# PiModulos_V2_-_Mayonaise.net
KiCad netlist of a schematic drawn in Altium Designer
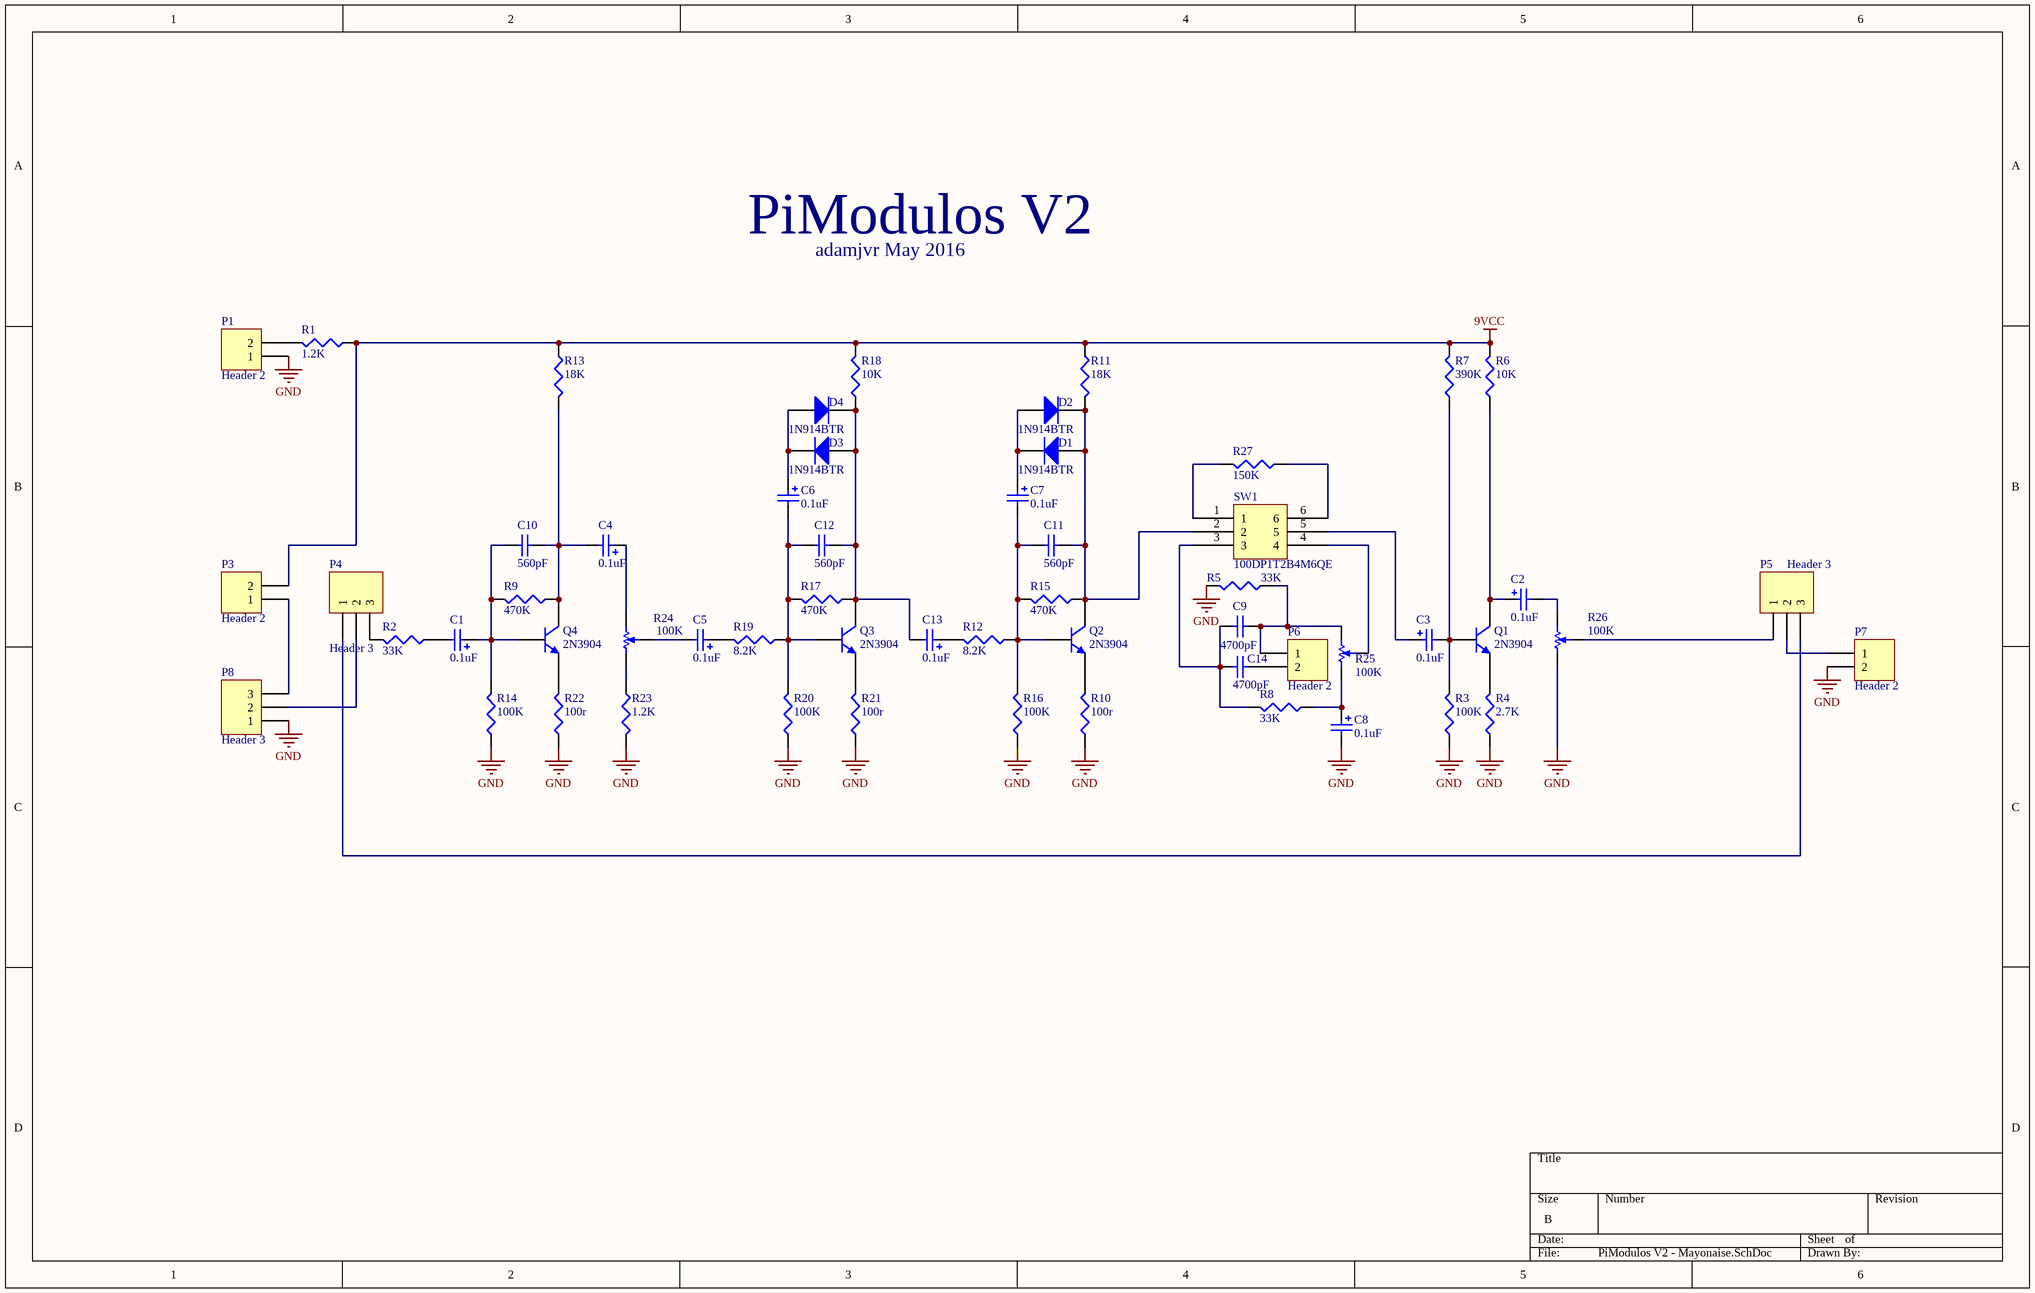
[diagram p0: PiModulos V2 - Mayonaise.SchDoc]

(export (version "E")
  (design (tool "Eeschema 10.0.6"))
  (components
    (comp (ref "C1")
      (value "0.1uF")
      (footprint "5X12.5mmCAP")
      (description "CAP ALUM 0.1UF 20% 100V RADIAL")
      (fields
        (field (name "MFR") "Nichicon")
        (field (name "TOLERANCE") "20%")
        (field (name "DESIGNER") "Adam Vadala-Roth")
      )
      (libsource (lib "AudioPartLib") (part "UFG2A0R1MDM1TD"))
    )
    (comp (ref "C2")
      (value "0.1uF")
      (footprint "5X12.5mmCAP")
      (description "CAP ALUM 0.1UF 20% 100V RADIAL")
      (fields
        (field (name "MFR") "Nichicon")
        (field (name "TOLERANCE") "20%")
        (field (name "DESIGNER") "Adam Vadala-Roth")
      )
      (libsource (lib "AudioPartLib") (part "UFG2A0R1MDM1TD"))
    )
    (comp (ref "C3")
      (value "0.1uF")
      (footprint "5X12.5mmCAP")
      (description "CAP ALUM 0.1UF 20% 100V RADIAL")
      (fields
        (field (name "MFR") "Nichicon")
        (field (name "TOLERANCE") "20%")
        (field (name "DESIGNER") "Adam Vadala-Roth")
      )
      (libsource (lib "AudioPartLib") (part "UFG2A0R1MDM1TD"))
    )
    (comp (ref "C4")
      (value "0.1uF")
      (footprint "5X12.5mmCAP")
      (description "CAP ALUM 0.1UF 20% 100V RADIAL")
      (fields
        (field (name "MFR") "Nichicon")
        (field (name "TOLERANCE") "20%")
        (field (name "DESIGNER") "Adam Vadala-Roth")
      )
      (libsource (lib "AudioPartLib") (part "UFG2A0R1MDM1TD"))
    )
    (comp (ref "C5")
      (value "0.1uF")
      (footprint "5X12.5mmCAP")
      (description "CAP ALUM 0.1UF 20% 100V RADIAL")
      (fields
        (field (name "MFR") "Nichicon")
        (field (name "TOLERANCE") "20%")
        (field (name "DESIGNER") "Adam Vadala-Roth")
      )
      (libsource (lib "AudioPartLib") (part "UFG2A0R1MDM1TD"))
    )
    (comp (ref "C6")
      (value "0.1uF")
      (footprint "5X12.5mmCAP")
      (description "CAP ALUM 0.1UF 20% 100V RADIAL")
      (fields
        (field (name "MFR") "Nichicon")
        (field (name "TOLERANCE") "20%")
        (field (name "DESIGNER") "Adam Vadala-Roth")
      )
      (libsource (lib "AudioPartLib") (part "UFG2A0R1MDM1TD"))
    )
    (comp (ref "C7")
      (value "0.1uF")
      (footprint "5X12.5mmCAP")
      (description "CAP ALUM 0.1UF 20% 100V RADIAL")
      (fields
        (field (name "MFR") "Nichicon")
        (field (name "TOLERANCE") "20%")
        (field (name "DESIGNER") "Adam Vadala-Roth")
      )
      (libsource (lib "AudioPartLib") (part "UFG2A0R1MDM1TD"))
    )
    (comp (ref "C8")
      (value "0.1uF")
      (footprint "5X12.5mmCAP")
      (description "CAP ALUM 0.1UF 20% 100V RADIAL")
      (fields
        (field (name "MFR") "Nichicon")
        (field (name "TOLERANCE") "20%")
        (field (name "DESIGNER") "Adam Vadala-Roth")
      )
      (libsource (lib "AudioPartLib") (part "UFG2A0R1MDM1TD"))
    )
    (comp (ref "C9")
      (value "4700pF")
      (footprint "VY2472M49Y5US63V7")
      (fields
        (field (name "MFR") "Vishay-BC-Components")
        (field (name "TOLERANCE") "20%")
        (field (name "VOLTAGE") "440VAC")
        (field (name "DESIGNER") "Adam Vadala-Roth")
      )
      (libsource (lib "AudioPartLib") (part "VY2472M49Y5US63V7"))
    )
    (comp (ref "C10")
      (value "560pF")
      (footprint "C0805")
      (fields
        (field (name "MFR") "Samsung-Electro-Mechanics-America,-Inc.")
        (field (name "TOLERANCE") "5%")
        (field (name "VOLTAGE") "50V")
        (field (name "DESIGNER") "Adam Vadala-Roth")
      )
      (libsource (lib "AudioPartLib") (part "CL21C561JBANNNC"))
    )
    (comp (ref "C11")
      (value "560pF")
      (footprint "C0805")
      (fields
        (field (name "MFR") "Samsung-Electro-Mechanics-America,-Inc.")
        (field (name "TOLERANCE") "5%")
        (field (name "VOLTAGE") "50V")
        (field (name "DESIGNER") "Adam Vadala-Roth")
      )
      (libsource (lib "AudioPartLib") (part "CL21C561JBANNNC"))
    )
    (comp (ref "C12")
      (value "560pF")
      (footprint "C0805")
      (fields
        (field (name "MFR") "Samsung-Electro-Mechanics-America,-Inc.")
        (field (name "TOLERANCE") "5%")
        (field (name "VOLTAGE") "50V")
        (field (name "DESIGNER") "Adam Vadala-Roth")
      )
      (libsource (lib "AudioPartLib") (part "CL21C561JBANNNC"))
    )
    (comp (ref "C13")
      (value "0.1uF")
      (footprint "5X12.5mmCAP")
      (description "CAP ALUM 0.1UF 20% 100V RADIAL")
      (fields
        (field (name "MFR") "Nichicon")
        (field (name "TOLERANCE") "20%")
        (field (name "DESIGNER") "Adam Vadala-Roth")
      )
      (libsource (lib "AudioPartLib") (part "UFG2A0R1MDM1TD"))
    )
    (comp (ref "C14")
      (value "4700pF")
      (footprint "VY2472M49Y5US63V7")
      (fields
        (field (name "MFR") "Vishay-BC-Components")
        (field (name "TOLERANCE") "20%")
        (field (name "VOLTAGE") "440VAC")
        (field (name "DESIGNER") "Adam Vadala-Roth")
      )
      (libsource (lib "AudioPartLib") (part "VY2472M49Y5US63V7"))
    )
    (comp (ref "D1")
      (value "1N914BTR")
      (footprint "DO-35")
      (description "DIODE GEN PURP 100V 200MA DO35")
      (fields
        (field (name "MFR") "Fairchild-Semiconductor")
        (field (name "VOLTAGE") "100V")
        (field (name "DESIGNER") "Adam Vadala-Roth")
      )
      (libsource (lib "AudioPartLib") (part "1N914BTR"))
    )
    (comp (ref "D2")
      (value "1N914BTR")
      (footprint "DO-35")
      (description "DIODE GEN PURP 100V 200MA DO35")
      (fields
        (field (name "MFR") "Fairchild-Semiconductor")
        (field (name "VOLTAGE") "100V")
        (field (name "DESIGNER") "Adam Vadala-Roth")
      )
      (libsource (lib "AudioPartLib") (part "1N914BTR"))
    )
    (comp (ref "D3")
      (value "1N914BTR")
      (footprint "DO-35")
      (description "DIODE GEN PURP 100V 200MA DO35")
      (fields
        (field (name "MFR") "Fairchild-Semiconductor")
        (field (name "VOLTAGE") "100V")
        (field (name "DESIGNER") "Adam Vadala-Roth")
      )
      (libsource (lib "AudioPartLib") (part "1N914BTR"))
    )
    (comp (ref "D4")
      (value "1N914BTR")
      (footprint "DO-35")
      (description "DIODE GEN PURP 100V 200MA DO35")
      (fields
        (field (name "MFR") "Fairchild-Semiconductor")
        (field (name "VOLTAGE") "100V")
        (field (name "DESIGNER") "Adam Vadala-Roth")
      )
      (libsource (lib "AudioPartLib") (part "1N914BTR"))
    )
    (comp (ref "P1")
      (value "Header 2")
      (footprint "HDR1X2")
      (description "Header, 2-Pin")
      (fields (field (name "PUBLISHER") "Altium Limited"))
      (libsource (lib "") (part "Header 2_1"))
    )
    (comp (ref "P3")
      (value "Header 2")
      (footprint "HDR1X2")
      (description "Header, 2-Pin")
      (fields (field (name "PUBLISHER") "Altium Limited"))
      (libsource (lib "") (part "Header 2_1"))
    )
    (comp (ref "P4")
      (value "Header 3")
      (footprint "HDR1X3")
      (description "Header, 3-Pin")
      (fields (field (name "PUBLISHER") "Altium Limited"))
      (libsource (lib "Miscellaneous Connectors") (part "Header 3"))
    )
    (comp (ref "P5")
      (value "Header 3")
      (footprint "HDR1X3")
      (description "Header, 3-Pin")
      (fields (field (name "PUBLISHER") "Altium Limited"))
      (libsource (lib "Miscellaneous Connectors") (part "Header 3"))
    )
    (comp (ref "P6")
      (value "Header 2")
      (footprint "HDR1X2")
      (description "Header, 2-Pin")
      (fields (field (name "PUBLISHER") "Altium Limited"))
      (libsource (lib "Miscellaneous Connectors") (part "Header 2"))
    )
    (comp (ref "P7")
      (value "Header 2")
      (footprint "HDR1X2")
      (description "Header, 2-Pin")
      (fields (field (name "PUBLISHER") "Altium Limited"))
      (libsource (lib "Miscellaneous Connectors") (part "Header 2"))
    )
    (comp (ref "P8")
      (value "Header 3")
      (footprint "HDR1X3")
      (description "Header, 3-Pin")
      (fields (field (name "PUBLISHER") "Altium Limited"))
      (libsource (lib "") (part "Header 3_1"))
    )
    (comp (ref "Q1")
      (value "2N3904")
      (footprint "TO-92A")
      (description "TRANS NPN 40V 0.2A TO-92")
      (fields
        (field (name "MFR") "Fairchild-Semiconductor")
        (field (name "VOLTAGE") "40V")
        (field (name "DESIGNER") "Adam Vadala-Roth")
      )
      (libsource (lib "AudioPartLib") (part "2N3904TF"))
    )
    (comp (ref "Q2")
      (value "2N3904")
      (footprint "TO-92A")
      (description "TRANS NPN 40V 0.2A TO-92")
      (fields
        (field (name "MFR") "Fairchild-Semiconductor")
        (field (name "VOLTAGE") "40V")
        (field (name "DESIGNER") "Adam Vadala-Roth")
      )
      (libsource (lib "AudioPartLib") (part "2N3904TF"))
    )
    (comp (ref "Q3")
      (value "2N3904")
      (footprint "TO-92A")
      (description "TRANS NPN 40V 0.2A TO-92")
      (fields
        (field (name "MFR") "Fairchild-Semiconductor")
        (field (name "VOLTAGE") "40V")
        (field (name "DESIGNER") "Adam Vadala-Roth")
      )
      (libsource (lib "AudioPartLib") (part "2N3904TF"))
    )
    (comp (ref "Q4")
      (value "2N3904")
      (footprint "TO-92A")
      (description "TRANS NPN 40V 0.2A TO-92")
      (fields
        (field (name "MFR") "Fairchild-Semiconductor")
        (field (name "VOLTAGE") "40V")
        (field (name "DESIGNER") "Adam Vadala-Roth")
      )
      (libsource (lib "AudioPartLib") (part "2N3904TF"))
    )
    (comp (ref "R1")
      (value "1.2K")
      (footprint "R0805")
      (description "RES SMD 1.2K OHM 1% 1/8W 0805")
      (fields
        (field (name "MFR") "Panasonic-Electronic-Components")
        (field (name "TOLERANCE") "1%")
        (field (name "DESIGNER") "Adam Vadala-Roth")
      )
      (libsource (lib "AudioPartLib") (part "ERJ-6ENF1201V"))
    )
    (comp (ref "R2")
      (value "33K")
      (footprint "R0805")
      (description "RES SMD 33K OHM 1% 1/8W 0805")
      (fields
        (field (name "MFR") "Panasonic-Electronic-Components")
        (field (name "TOLERANCE") "1%")
        (field (name "DESIGNER") "Adam Vadala-Roth")
      )
      (libsource (lib "AudioPartLib") (part "ERJ-6ENF3302V"))
    )
    (comp (ref "R3")
      (value "100K")
      (footprint "R0805")
      (description "RES SMD 100K OHM 1% 1/8W 0805")
      (fields
        (field (name "MFR") "Panasonic-Electronic-Components")
        (field (name "TOLERANCE") "1%")
        (field (name "DESIGNER") "Adam Vadala-Roth")
      )
      (libsource (lib "AudioPartLib") (part "ERJ-6ENF1003V"))
    )
    (comp (ref "R4")
      (value "2.7K")
      (footprint "R0805")
      (description "RES SMD 2.7K OHM 1% 1/8W 0805")
      (fields
        (field (name "MFR") "Samsung-Electro-Mechanics-America,-Inc.")
        (field (name "TOLERANCE") "1%")
        (field (name "DESIGNER") "Adam Vadala-Roth")
      )
      (libsource (lib "AudioPartLib") (part "RC2012F272CS"))
    )
    (comp (ref "R5")
      (value "33K")
      (footprint "R0805")
      (description "RES SMD 33K OHM 1% 1/8W 0805")
      (fields
        (field (name "MFR") "Panasonic-Electronic-Components")
        (field (name "TOLERANCE") "1%")
        (field (name "DESIGNER") "Adam Vadala-Roth")
      )
      (libsource (lib "AudioPartLib") (part "ERJ-6ENF3302V"))
    )
    (comp (ref "R6")
      (value "10K")
      (footprint "R0805")
      (description "RES SMD 10K OHM 1% 1/8W 0805")
      (fields
        (field (name "MFR") "Panasonic-Electronic-Components")
        (field (name "TOLERANCE") "1%")
        (field (name "DESIGNER") "Adam Vadala-Roth")
      )
      (libsource (lib "AudioPartLib") (part "ERJ-6ENF1002V"))
    )
    (comp (ref "R7")
      (value "390K")
      (footprint "R0805")
      (description "RES SMD 390K OHM 1% 1/8W 0805")
      (fields
        (field (name "MFR") "Panasonic-Electronic-Components")
        (field (name "TOLERANCE") "1%")
        (field (name "DESIGNER") "Adam Vadala-Roth")
      )
      (libsource (lib "AudioPartLib") (part "ERJ-6ENF3903V"))
    )
    (comp (ref "R8")
      (value "33K")
      (footprint "R0805")
      (description "RES SMD 33K OHM 1% 1/8W 0805")
      (fields
        (field (name "MFR") "Panasonic-Electronic-Components")
        (field (name "TOLERANCE") "1%")
        (field (name "DESIGNER") "Adam Vadala-Roth")
      )
      (libsource (lib "AudioPartLib") (part "ERJ-6ENF3302V"))
    )
    (comp (ref "R9")
      (value "470K")
      (footprint "R0805")
      (description "RES SMD 470K OHM 1% 1/8W 0805")
      (fields
        (field (name "MFR") "Panasonic-Electronic-Components")
        (field (name "TOLERANCE") "1%")
        (field (name "DESIGNER") "Adam Vadala-Roth")
      )
      (libsource (lib "AudioPartLib") (part "ERJ-6ENF4703V"))
    )
    (comp (ref "R10")
      (value "100r")
      (footprint "R0805")
      (description "RES SMD 100 OHM 1% 1/8W 0805")
      (fields
        (field (name "MFR") "Vishay-Dale")
        (field (name "TOLERANCE") "1%")
        (field (name "DESIGNER") "Adam Vadala-Roth")
      )
      (libsource (lib "AudioPartLib") (part "CRCW0805100RFKEA"))
    )
    (comp (ref "R11")
      (value "18K")
      (footprint "R0805")
      (description "RES SMD 18K OHM 1% 1/8W 0805")
      (fields
        (field (name "MFR") "Panasonic-Electronic-Components")
        (field (name "TOLERANCE") "1%")
        (field (name "DESIGNER") "Adam Vadala-Roth")
      )
      (libsource (lib "AudioPartLib") (part "ERJ-6ENF1802V"))
    )
    (comp (ref "R12")
      (value "8.2K")
      (footprint "R0805")
      (description "RES SMD 8.2K OHM 1% 1/8W 0805")
      (fields
        (field (name "MFR") "Samsung-Electro-Mechanics-America,-Inc.")
        (field (name "TOLERANCE") "1%")
        (field (name "DESIGNER") "Adam Vadala-Roth")
      )
      (libsource (lib "AudioPartLib") (part "RC2012F822CS"))
    )
    (comp (ref "R13")
      (value "18K")
      (footprint "R0805")
      (description "RES SMD 18K OHM 1% 1/8W 0805")
      (fields
        (field (name "MFR") "Panasonic-Electronic-Components")
        (field (name "TOLERANCE") "1%")
        (field (name "DESIGNER") "Adam Vadala-Roth")
      )
      (libsource (lib "AudioPartLib") (part "ERJ-6ENF1802V"))
    )
    (comp (ref "R14")
      (value "100K")
      (footprint "R0805")
      (description "RES SMD 100K OHM 1% 1/8W 0805")
      (fields
        (field (name "MFR") "Panasonic-Electronic-Components")
        (field (name "TOLERANCE") "1%")
        (field (name "DESIGNER") "Adam Vadala-Roth")
      )
      (libsource (lib "AudioPartLib") (part "ERJ-6ENF1003V"))
    )
    (comp (ref "R15")
      (value "470K")
      (footprint "R0805")
      (description "RES SMD 470K OHM 1% 1/8W 0805")
      (fields
        (field (name "MFR") "Panasonic-Electronic-Components")
        (field (name "TOLERANCE") "1%")
        (field (name "DESIGNER") "Adam Vadala-Roth")
      )
      (libsource (lib "AudioPartLib") (part "ERJ-6ENF4703V"))
    )
    (comp (ref "R16")
      (value "100K")
      (footprint "R0805")
      (description "RES SMD 100K OHM 1% 1/8W 0805")
      (fields
        (field (name "MFR") "Panasonic-Electronic-Components")
        (field (name "TOLERANCE") "1%")
        (field (name "DESIGNER") "Adam Vadala-Roth")
      )
      (libsource (lib "AudioPartLib") (part "ERJ-6ENF1003V"))
    )
    (comp (ref "R17")
      (value "470K")
      (footprint "R0805")
      (description "RES SMD 470K OHM 1% 1/8W 0805")
      (fields
        (field (name "MFR") "Panasonic-Electronic-Components")
        (field (name "TOLERANCE") "1%")
        (field (name "DESIGNER") "Adam Vadala-Roth")
      )
      (libsource (lib "AudioPartLib") (part "ERJ-6ENF4703V"))
    )
    (comp (ref "R18")
      (value "10K")
      (footprint "R0805")
      (description "RES SMD 10K OHM 1% 1/8W 0805")
      (fields
        (field (name "MFR") "Panasonic-Electronic-Components")
        (field (name "TOLERANCE") "1%")
        (field (name "DESIGNER") "Adam Vadala-Roth")
      )
      (libsource (lib "AudioPartLib") (part "ERJ-6ENF1002V"))
    )
    (comp (ref "R19")
      (value "8.2K")
      (footprint "R0805")
      (description "RES SMD 8.2K OHM 1% 1/8W 0805")
      (fields
        (field (name "MFR") "Samsung-Electro-Mechanics-America,-Inc.")
        (field (name "TOLERANCE") "1%")
        (field (name "DESIGNER") "Adam Vadala-Roth")
      )
      (libsource (lib "AudioPartLib") (part "RC2012F822CS"))
    )
    (comp (ref "R20")
      (value "100K")
      (footprint "R0805")
      (description "RES SMD 100K OHM 1% 1/8W 0805")
      (fields
        (field (name "MFR") "Panasonic-Electronic-Components")
        (field (name "TOLERANCE") "1%")
        (field (name "DESIGNER") "Adam Vadala-Roth")
      )
      (libsource (lib "AudioPartLib") (part "ERJ-6ENF1003V"))
    )
    (comp (ref "R21")
      (value "100r")
      (footprint "R0805")
      (description "RES SMD 100 OHM 1% 1/8W 0805")
      (fields
        (field (name "MFR") "Vishay-Dale")
        (field (name "TOLERANCE") "1%")
        (field (name "DESIGNER") "Adam Vadala-Roth")
      )
      (libsource (lib "AudioPartLib") (part "CRCW0805100RFKEA"))
    )
    (comp (ref "R22")
      (value "100r")
      (footprint "R0805")
      (description "RES SMD 100 OHM 1% 1/8W 0805")
      (fields
        (field (name "MFR") "Vishay-Dale")
        (field (name "TOLERANCE") "1%")
        (field (name "DESIGNER") "Adam Vadala-Roth")
      )
      (libsource (lib "AudioPartLib") (part "CRCW0805100RFKEA"))
    )
    (comp (ref "R23")
      (value "1.2K")
      (footprint "R0805")
      (description "RES SMD 1.2K OHM 1% 1/8W 0805")
      (fields
        (field (name "MFR") "Panasonic-Electronic-Components")
        (field (name "TOLERANCE") "1%")
        (field (name "DESIGNER") "Adam Vadala-Roth")
      )
      (libsource (lib "AudioPartLib") (part "ERJ-6ENF1201V"))
    )
    (comp (ref "R24")
      (value "100K")
      (footprint "BOURNS_PTD90SERIES_POT")
      (description "POT 100K OHM 1/20W CARBON LINEAR")
      (fields
        (field (name "MFR") "Bourns Inc.")
        (field (name "TOLERANCE") "20%")
        (field (name "DESIGNER") "Adam Vadala-Roth")
      )
      (libsource (lib "AudioPartLib") (part "PTD901-2015K-B104"))
    )
    (comp (ref "R25")
      (value "100K")
      (footprint "BOURNS_PTD90SERIES_POT")
      (description "POT 100K OHM 1/20W CARBON LINEAR")
      (fields
        (field (name "MFR") "Bourns Inc.")
        (field (name "TOLERANCE") "20%")
        (field (name "DESIGNER") "Adam Vadala-Roth")
      )
      (libsource (lib "AudioPartLib") (part "PTD901-2015K-B104"))
    )
    (comp (ref "R26")
      (value "100K")
      (footprint "BOURNS_PTD90SERIES_POT")
      (description "POT 100K OHM 1/20W CARBON LINEAR")
      (fields
        (field (name "MFR") "Bourns Inc.")
        (field (name "TOLERANCE") "20%")
        (field (name "DESIGNER") "Adam Vadala-Roth")
      )
      (libsource (lib "AudioPartLib") (part "PTD901-2015K-B104"))
    )
    (comp (ref "R27")
      (value "150K")
      (footprint "R0805")
      (description "RES SMD 150K OHM 1% 1/8W 0805")
      (fields
        (field (name "MFR") "Samsung-Electro-Mechanics-America,-Inc.")
        (field (name "TOLERANCE") "1%")
        (field (name "DESIGNER") "Adam Vadala-Roth")
      )
      (libsource (lib "AudioPartLib") (part "RC2012F154CS"))
    )
    (comp (ref "SW1")
      (value "100DP1T2B4M6QE")
      (footprint "100DP1T2B4M6QE")
      (description "SWITCH TOGGLE DPDT 5A 120V")
      (fields
        (field (name "MFR") "E-Switch")
        (field (name "VOLTAGE") "120V")
        (field (name "DESIGNER") "Adam Vadala-Roth")
      )
      (libsource (lib "AudioPartLib") (part "100DP1T2B4M6QE"))
    )
  )
  (nets
    (net (code "1") (name "9VCC") (class "Default")
      (node (ref "P3") (pin "2") (pinfunction "2_2") (pintype "passive"))
      (node (ref "R1") (pin "1") (pinfunction "1_1") (pintype "passive"))
      (node (ref "R11") (pin "1") (pinfunction "1_1") (pintype "passive"))
      (node (ref "R13") (pin "1") (pinfunction "1_1") (pintype "passive"))
      (node (ref "R18") (pin "2") (pinfunction "2_2") (pintype "passive"))
      (node (ref "R6") (pin "2") (pinfunction "2_2") (pintype "passive"))
      (node (ref "R7") (pin "2") (pinfunction "2_2") (pintype "passive"))
    )
    (net (code "2") (name "GND") (class "Default")
      (node (ref "C8") (pin "2") (pinfunction "2_2") (pintype "passive"))
      (node (ref "P1") (pin "1") (pinfunction "1_1") (pintype "passive"))
      (node (ref "P7") (pin "2") (pinfunction "2_2") (pintype "passive"))
      (node (ref "P8") (pin "1") (pinfunction "1_1") (pintype "passive"))
      (node (ref "R10") (pin "1") (pinfunction "1_1") (pintype "passive"))
      (node (ref "R14") (pin "1") (pinfunction "1_1") (pintype "passive"))
      (node (ref "R16") (pin "1") (pinfunction "1_1") (pintype "passive"))
      (node (ref "R20") (pin "1") (pinfunction "1_1") (pintype "passive"))
      (node (ref "R21") (pin "1") (pinfunction "1_1") (pintype "passive"))
      (node (ref "R22") (pin "1") (pinfunction "1_1") (pintype "passive"))
      (node (ref "R23") (pin "2") (pinfunction "2_2") (pintype "passive"))
      (node (ref "R26") (pin "3") (pinfunction "3_3") (pintype "passive"))
      (node (ref "R3") (pin "1") (pinfunction "1_1") (pintype "passive"))
      (node (ref "R4") (pin "1") (pinfunction "1_1") (pintype "passive"))
      (node (ref "R5") (pin "2") (pinfunction "2_2") (pintype "passive"))
    )
    (net (code "3") (name "Net-(C1-Pad2)") (class "Default")
      (node (ref "C1") (pin "2") (pinfunction "2_2") (pintype "passive"))
      (node (ref "R2") (pin "1") (pinfunction "1_1") (pintype "passive"))
    )
    (net (code "4") (name "Net-(C2-Pad2)") (class "Default")
      (node (ref "C2") (pin "2") (pinfunction "2_2") (pintype "passive"))
      (node (ref "R26") (pin "1") (pinfunction "1_1") (pintype "passive"))
    )
    (net (code "5") (name "Net-(C3-Pad1)") (class "Default")
      (node (ref "C3") (pin "1") (pinfunction "1_1") (pintype "passive"))
      (node (ref "SW1") (pin "5") (pinfunction "5_5") (pintype "passive"))
    )
    (net (code "6") (name "Net-(C4-Pad1)") (class "Default")
      (node (ref "C4") (pin "1") (pinfunction "1_1") (pintype "passive"))
      (node (ref "R24") (pin "1") (pinfunction "1_1") (pintype "passive"))
    )
    (net (code "7") (name "Net-(C5-Pad1)") (class "Default")
      (node (ref "C5") (pin "1") (pinfunction "1_1") (pintype "passive"))
      (node (ref "R19") (pin "2") (pinfunction "2_2") (pintype "passive"))
    )
    (net (code "8") (name "Net-(C5-Pad2)") (class "Default")
      (node (ref "C5") (pin "2") (pinfunction "2_2") (pintype "passive"))
      (node (ref "R24") (pin "2") (pinfunction "2_2") (pintype "passive"))
    )
    (net (code "9") (name "Net-(C8-Pad1)") (class "Default")
      (node (ref "C8") (pin "1") (pinfunction "1_1") (pintype "passive"))
      (node (ref "R25") (pin "3") (pinfunction "3_3") (pintype "passive"))
      (node (ref "R8") (pin "1") (pinfunction "1_1") (pintype "passive"))
    )
    (net (code "10") (name "Net-(C9-Pad1)") (class "Default")
      (node (ref "C9") (pin "1") (pinfunction "1_1") (pintype "passive"))
      (node (ref "P6") (pin "1") (pinfunction "1_1") (pintype "passive"))
      (node (ref "R25") (pin "1") (pinfunction "1_1") (pintype "passive"))
      (node (ref "R5") (pin "1") (pinfunction "1_1") (pintype "passive"))
    )
    (net (code "11") (name "Net-(C13-Pad1)") (class "Default")
      (node (ref "C13") (pin "1") (pinfunction "1_1") (pintype "passive"))
      (node (ref "R12") (pin "2") (pinfunction "2_2") (pintype "passive"))
    )
    (net (code "12") (name "Net-(C14-Pad1)") (class "Default")
      (node (ref "C14") (pin "1") (pinfunction "1_1") (pintype "passive"))
      (node (ref "P6") (pin "2") (pinfunction "2_2") (pintype "passive"))
    )
    (net (code "13") (name "Net-(C14-Pad2)") (class "Default")
      (node (ref "C14") (pin "2") (pinfunction "2_2") (pintype "passive"))
      (node (ref "C9") (pin "2") (pinfunction "2_2") (pintype "passive"))
      (node (ref "R8") (pin "2") (pinfunction "2_2") (pintype "passive"))
      (node (ref "SW1") (pin "3") (pinfunction "3_3") (pintype "passive"))
    )
    (net (code "14") (name "Net-(D1-A)") (class "Default")
      (node (ref "C11") (pin "1") (pinfunction "1_1") (pintype "passive"))
      (node (ref "D1") (pin "1") (pinfunction "A_1") (pintype "passive"))
      (node (ref "D2") (pin "2") (pinfunction "K_2") (pintype "passive"))
      (node (ref "Q2") (pin "3") (pinfunction "C_3") (pintype "passive"))
      (node (ref "R11") (pin "2") (pinfunction "2_2") (pintype "passive"))
      (node (ref "R15") (pin "1") (pinfunction "1_1") (pintype "passive"))
      (node (ref "SW1") (pin "2") (pinfunction "2_2") (pintype "passive"))
    )
    (net (code "15") (name "Net-(D1-K)") (class "Default")
      (node (ref "C7") (pin "1") (pinfunction "1_1") (pintype "passive"))
      (node (ref "D1") (pin "2") (pinfunction "K_2") (pintype "passive"))
      (node (ref "D2") (pin "1") (pinfunction "A_1") (pintype "passive"))
    )
    (net (code "16") (name "Net-(D3-A)") (class "Default")
      (node (ref "C12") (pin "1") (pinfunction "1_1") (pintype "passive"))
      (node (ref "C13") (pin "2") (pinfunction "2_2") (pintype "passive"))
      (node (ref "D3") (pin "1") (pinfunction "A_1") (pintype "passive"))
      (node (ref "D4") (pin "2") (pinfunction "K_2") (pintype "passive"))
      (node (ref "Q3") (pin "3") (pinfunction "C_3") (pintype "passive"))
      (node (ref "R17") (pin "1") (pinfunction "1_1") (pintype "passive"))
      (node (ref "R18") (pin "1") (pinfunction "1_1") (pintype "passive"))
    )
    (net (code "17") (name "Net-(D3-K)") (class "Default")
      (node (ref "C6") (pin "1") (pinfunction "1_1") (pintype "passive"))
      (node (ref "D3") (pin "2") (pinfunction "K_2") (pintype "passive"))
      (node (ref "D4") (pin "1") (pinfunction "A_1") (pintype "passive"))
    )
    (net (code "18") (name "Net-(P1-Pad2)") (class "Default")
      (node (ref "P1") (pin "2") (pinfunction "2_2") (pintype "passive"))
      (node (ref "R1") (pin "2") (pinfunction "2_2") (pintype "passive"))
    )
    (net (code "19") (name "Net-(P3-Pad1)") (class "Default")
      (node (ref "P3") (pin "1") (pinfunction "1_1") (pintype "passive"))
      (node (ref "P8") (pin "3") (pinfunction "3_3") (pintype "passive"))
    )
    (net (code "20") (name "Net-(P4-Pad1)") (class "Default")
      (node (ref "P4") (pin "1") (pinfunction "1_1") (pintype "passive"))
      (node (ref "P5") (pin "3") (pinfunction "3_3") (pintype "passive"))
    )
    (net (code "21") (name "Net-(P4-Pad2)") (class "Default")
      (node (ref "P4") (pin "2") (pinfunction "2_2") (pintype "passive"))
      (node (ref "P8") (pin "2") (pinfunction "2_2") (pintype "passive"))
    )
    (net (code "22") (name "Net-(P4-Pad3)") (class "Default")
      (node (ref "P4") (pin "3") (pinfunction "3_3") (pintype "passive"))
      (node (ref "R2") (pin "2") (pinfunction "2_2") (pintype "passive"))
    )
    (net (code "23") (name "Net-(P5-Pad1)") (class "Default")
      (node (ref "P5") (pin "1") (pinfunction "1_1") (pintype "passive"))
      (node (ref "R26") (pin "2") (pinfunction "2_2") (pintype "passive"))
    )
    (net (code "24") (name "Net-(P5-Pad2)") (class "Default")
      (node (ref "P5") (pin "2") (pinfunction "2_2") (pintype "passive"))
      (node (ref "P7") (pin "1") (pinfunction "1_1") (pintype "passive"))
    )
    (net (code "25") (name "Net-(Q1-B)") (class "Default")
      (node (ref "C3") (pin "2") (pinfunction "2_2") (pintype "passive"))
      (node (ref "Q1") (pin "2") (pinfunction "B_2") (pintype "passive"))
      (node (ref "R3") (pin "2") (pinfunction "2_2") (pintype "passive"))
      (node (ref "R7") (pin "1") (pinfunction "1_1") (pintype "passive"))
    )
    (net (code "26") (name "Net-(Q1-C)") (class "Default")
      (node (ref "C2") (pin "1") (pinfunction "1_1") (pintype "passive"))
      (node (ref "Q1") (pin "3") (pinfunction "C_3") (pintype "passive"))
      (node (ref "R6") (pin "1") (pinfunction "1_1") (pintype "passive"))
    )
    (net (code "27") (name "Net-(Q1-E)") (class "Default")
      (node (ref "Q1") (pin "1") (pinfunction "E_1") (pintype "passive"))
      (node (ref "R4") (pin "2") (pinfunction "2_2") (pintype "passive"))
    )
    (net (code "28") (name "Net-(Q2-B)") (class "Default")
      (node (ref "C11") (pin "2") (pinfunction "2_2") (pintype "passive"))
      (node (ref "C7") (pin "2") (pinfunction "2_2") (pintype "passive"))
      (node (ref "Q2") (pin "2") (pinfunction "B_2") (pintype "passive"))
      (node (ref "R12") (pin "1") (pinfunction "1_1") (pintype "passive"))
      (node (ref "R15") (pin "2") (pinfunction "2_2") (pintype "passive"))
      (node (ref "R16") (pin "2") (pinfunction "2_2") (pintype "passive"))
    )
    (net (code "29") (name "Net-(Q2-E)") (class "Default")
      (node (ref "Q2") (pin "1") (pinfunction "E_1") (pintype "passive"))
      (node (ref "R10") (pin "2") (pinfunction "2_2") (pintype "passive"))
    )
    (net (code "30") (name "Net-(Q3-B)") (class "Default")
      (node (ref "C12") (pin "2") (pinfunction "2_2") (pintype "passive"))
      (node (ref "C6") (pin "2") (pinfunction "2_2") (pintype "passive"))
      (node (ref "Q3") (pin "2") (pinfunction "B_2") (pintype "passive"))
      (node (ref "R17") (pin "2") (pinfunction "2_2") (pintype "passive"))
      (node (ref "R19") (pin "1") (pinfunction "1_1") (pintype "passive"))
      (node (ref "R20") (pin "2") (pinfunction "2_2") (pintype "passive"))
    )
    (net (code "31") (name "Net-(Q3-E)") (class "Default")
      (node (ref "Q3") (pin "1") (pinfunction "E_1") (pintype "passive"))
      (node (ref "R21") (pin "2") (pinfunction "2_2") (pintype "passive"))
    )
    (net (code "32") (name "Net-(Q4-B)") (class "Default")
      (node (ref "C1") (pin "1") (pinfunction "1_1") (pintype "passive"))
      (node (ref "C10") (pin "2") (pinfunction "2_2") (pintype "passive"))
      (node (ref "Q4") (pin "2") (pinfunction "B_2") (pintype "passive"))
      (node (ref "R14") (pin "2") (pinfunction "2_2") (pintype "passive"))
      (node (ref "R9") (pin "2") (pinfunction "2_2") (pintype "passive"))
    )
    (net (code "33") (name "Net-(Q4-C)") (class "Default")
      (node (ref "C10") (pin "1") (pinfunction "1_1") (pintype "passive"))
      (node (ref "C4") (pin "2") (pinfunction "2_2") (pintype "passive"))
      (node (ref "Q4") (pin "3") (pinfunction "C_3") (pintype "passive"))
      (node (ref "R13") (pin "2") (pinfunction "2_2") (pintype "passive"))
      (node (ref "R9") (pin "1") (pinfunction "1_1") (pintype "passive"))
    )
    (net (code "34") (name "Net-(Q4-E)") (class "Default")
      (node (ref "Q4") (pin "1") (pinfunction "E_1") (pintype "passive"))
      (node (ref "R22") (pin "2") (pinfunction "2_2") (pintype "passive"))
    )
    (net (code "35") (name "Net-(R23-Pad1)") (class "Default")
      (node (ref "R23") (pin "1") (pinfunction "1_1") (pintype "passive"))
      (node (ref "R24") (pin "3") (pinfunction "3_3") (pintype "passive"))
    )
    (net (code "36") (name "Net-(R25-Pad2)") (class "Default")
      (node (ref "R25") (pin "2") (pinfunction "2_2") (pintype "passive"))
      (node (ref "SW1") (pin "4") (pinfunction "4_4") (pintype "passive"))
    )
    (net (code "37") (name "Net-(R27-Pad1)") (class "Default")
      (node (ref "R27") (pin "1") (pinfunction "1_1") (pintype "passive"))
      (node (ref "SW1") (pin "6") (pinfunction "6_6") (pintype "passive"))
    )
    (net (code "38") (name "Net-(R27-Pad2)") (class "Default")
      (node (ref "R27") (pin "2") (pinfunction "2_2") (pintype "passive"))
      (node (ref "SW1") (pin "1") (pinfunction "1_1") (pintype "passive"))
    )
  )
)
